# Motor_S_r_c.net
KiCad netlist of a schematic drawn in EAGLE
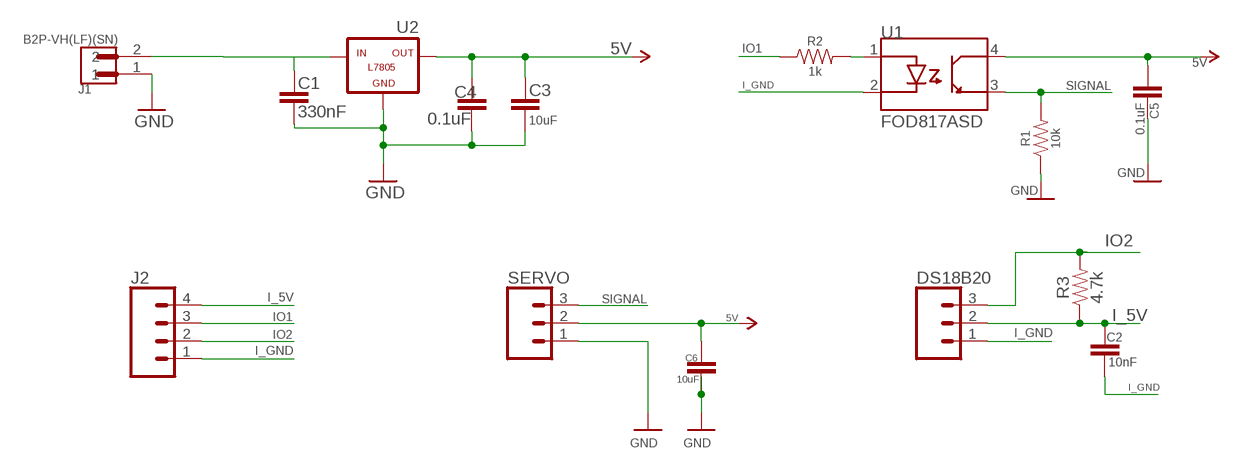
[diagram p0: schematic, sheet 1]

(export (version "E")
  (design (tool "Eeschema 10.0.6"))
  (components
    (comp (ref "C1")
      (value "330nF")
      (footprint "eagle-import:0603")
      (libsource (lib "eagle-import") (part "0.1UF-0603-25V-(+80/-20%)"))
    )
    (comp (ref "C2")
      (value "10nF")
      (footprint "eagle-import:0603")
      (libsource (lib "eagle-import") (part "0.1UF-0603-25V-(+80/-20%)"))
    )
    (comp (ref "C3")
      (value "10uF")
      (footprint "eagle-import:0603")
      (libsource (lib "eagle-import") (part "0.1UF-0603-25V-(+80/-20%)"))
    )
    (comp (ref "C4")
      (value "0.1uF")
      (footprint "eagle-import:0603")
      (libsource (lib "eagle-import") (part "0.1UF-0603-25V-(+80/-20%)"))
    )
    (comp (ref "C5")
      (value "0.1uF")
      (footprint "eagle-import:0603")
      (libsource (lib "eagle-import") (part "0.1UF-0603-25V-(+80/-20%)"))
    )
    (comp (ref "C6")
      (value "10uF")
      (footprint "eagle-import:0603")
      (libsource (lib "eagle-import") (part "0.1UF-0603-25V-(+80/-20%)"))
    )
    (comp (ref "DS18B20")
      (value "CONN_03")
      (footprint "eagle-import:1X03")
      (libsource (lib "eagle-import") (part "CONN_03"))
    )
    (comp (ref "J1")
      (value "B2P-VH(LF)(SN)")
      (footprint "eagle-import:JST_B2P-VH(LF)(SN)")
      (fields (field (name "MF") "JST Sales"))
      (libsource (lib "eagle-import") (part "B2P-VH(LF)(SN)"))
    )
    (comp (ref "J2")
      (value "CONN_04")
      (footprint "eagle-import:1X04")
      (libsource (lib "eagle-import") (part "CONN_04"))
    )
    (comp (ref "R1")
      (value "10k")
      (footprint "eagle-import:0603")
      (libsource (lib "eagle-import") (part "4.7KOHM-0603-1/10W-1%"))
    )
    (comp (ref "R2")
      (value "1k")
      (footprint "eagle-import:0603")
      (libsource (lib "eagle-import") (part "4.7KOHM-0603-1/10W-1%"))
    )
    (comp (ref "R3")
      (value "4.7k")
      (footprint "eagle-import:0603")
      (libsource (lib "eagle-import") (part "4.7KOHM-0603-1/10W-1%"))
    )
    (comp (ref "SERVO")
      (value "CONN_03")
      (footprint "eagle-import:1X03")
      (libsource (lib "eagle-import") (part "CONN_03"))
    )
    (comp (ref "U1")
      (value "FOD817ASD")
      (footprint "eagle-import:SOIC254P1016X385-4N")
      (fields (field (name "MF") "ON Semiconductor"))
      (libsource (lib "eagle-import") (part "FOD817ASD"))
    )
    (comp (ref "U2")
      (value "L7805")
      (footprint "eagle-import:78XXL")
      (libsource (lib "eagle-import") (part "L7805"))
    )
  )
  (nets
    (net (code "1") (name "/IO1") (class "Default")
      (node (ref "J2") (pin "3") (pinfunction "3_3") (pintype "passive"))
      (node (ref "R2") (pin "1") (pinfunction "1_1") (pintype "passive"))
    )
    (net (code "2") (name "/IO2") (class "Default")
      (node (ref "DS18B20") (pin "3") (pinfunction "3_3") (pintype "passive"))
      (node (ref "J2") (pin "2") (pinfunction "2_2") (pintype "passive"))
      (node (ref "R3") (pin "2") (pinfunction "2_2") (pintype "passive"))
    )
    (net (code "3") (name "/I_5V") (class "Default")
      (node (ref "C2") (pin "1") (pinfunction "1_1") (pintype "passive"))
      (node (ref "DS18B20") (pin "2") (pinfunction "2_2") (pintype "passive"))
      (node (ref "J2") (pin "4") (pinfunction "4_4") (pintype "passive"))
      (node (ref "R3") (pin "1") (pinfunction "1_1") (pintype "passive"))
    )
    (net (code "4") (name "/I_GND") (class "Default")
      (node (ref "C2") (pin "2") (pinfunction "2_2") (pintype "passive"))
      (node (ref "DS18B20") (pin "1") (pinfunction "1_1") (pintype "passive"))
      (node (ref "J2") (pin "1") (pinfunction "1_1") (pintype "passive"))
      (node (ref "U1") (pin "2") (pinfunction "CATHODE_2") (pintype "passive"))
    )
    (net (code "5") (name "/SIGNAL") (class "Default")
      (node (ref "R1") (pin "2") (pinfunction "2_2") (pintype "passive"))
      (node (ref "SERVO") (pin "3") (pinfunction "3_3") (pintype "passive"))
      (node (ref "U1") (pin "3") (pinfunction "EMITTER_3") (pintype "passive"))
    )
    (net (code "6") (name "5V") (class "Default")
      (node (ref "C3") (pin "1") (pinfunction "1_1") (pintype "passive"))
      (node (ref "C4") (pin "1") (pinfunction "1_1") (pintype "passive"))
      (node (ref "C5") (pin "2") (pinfunction "2_2") (pintype "passive"))
      (node (ref "C6") (pin "1") (pinfunction "1_1") (pintype "passive"))
      (node (ref "SERVO") (pin "2") (pinfunction "2_2") (pintype "passive"))
      (node (ref "U1") (pin "4") (pinfunction "COLLECTOR_4") (pintype "passive"))
      (node (ref "U2") (pin "OUT") (pinfunction "OUT_OUT") (pintype "passive"))
    )
    (net (code "7") (name "GND") (class "Default")
      (node (ref "C1") (pin "2") (pinfunction "2_2") (pintype "passive"))
      (node (ref "C3") (pin "2") (pinfunction "2_2") (pintype "passive"))
      (node (ref "C4") (pin "2") (pinfunction "2_2") (pintype "passive"))
      (node (ref "C5") (pin "1") (pinfunction "1_1") (pintype "passive"))
      (node (ref "C6") (pin "2") (pinfunction "2_2") (pintype "passive"))
      (node (ref "J1") (pin "1") (pinfunction "1_1") (pintype "passive"))
      (node (ref "R1") (pin "1") (pinfunction "1_1") (pintype "passive"))
      (node (ref "SERVO") (pin "1") (pinfunction "1_1") (pintype "passive"))
      (node (ref "U2") (pin "GND") (pinfunction "GND_GND") (pintype "input"))
    )
    (net (code "8") (name "Net-(C1-Pad1)") (class "Default")
      (node (ref "C1") (pin "1") (pinfunction "1_1") (pintype "passive"))
      (node (ref "J1") (pin "2") (pinfunction "2_2") (pintype "passive"))
      (node (ref "U2") (pin "IN") (pinfunction "IN_IN") (pintype "input"))
    )
    (net (code "9") (name "Net-(U1-ANODE)") (class "Default")
      (node (ref "R2") (pin "2") (pinfunction "2_2") (pintype "passive"))
      (node (ref "U1") (pin "1") (pinfunction "ANODE_1") (pintype "passive"))
    )
  )
)
